# VM3300_V0_1.net
KiCad netlist of a schematic drawn in Altium Designer
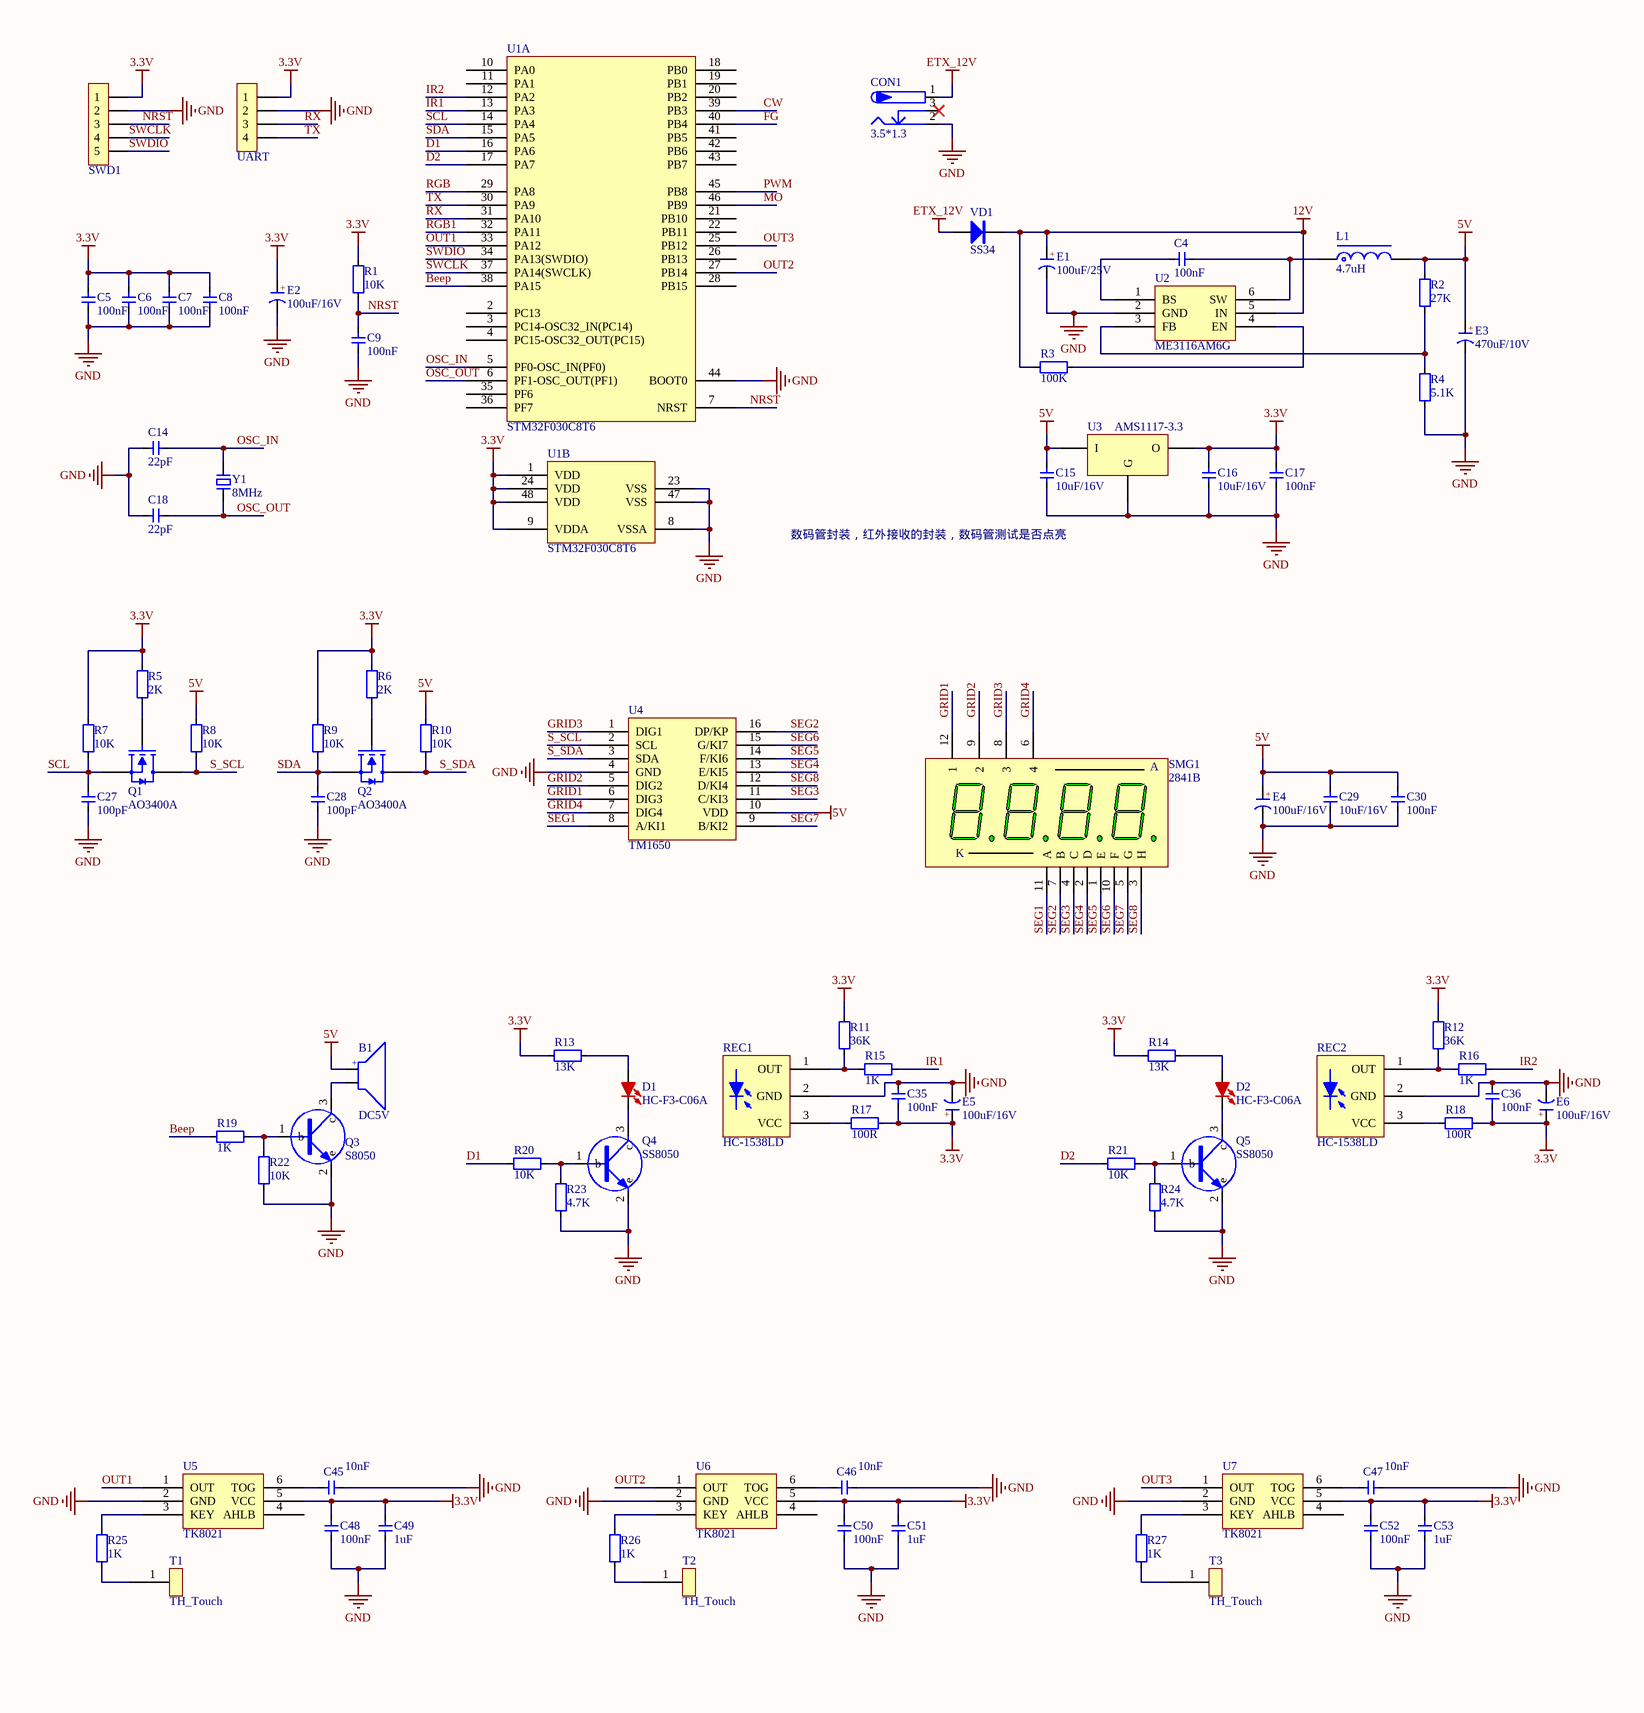
[diagram p0: VM3300_V0.1.SchDoc, left]
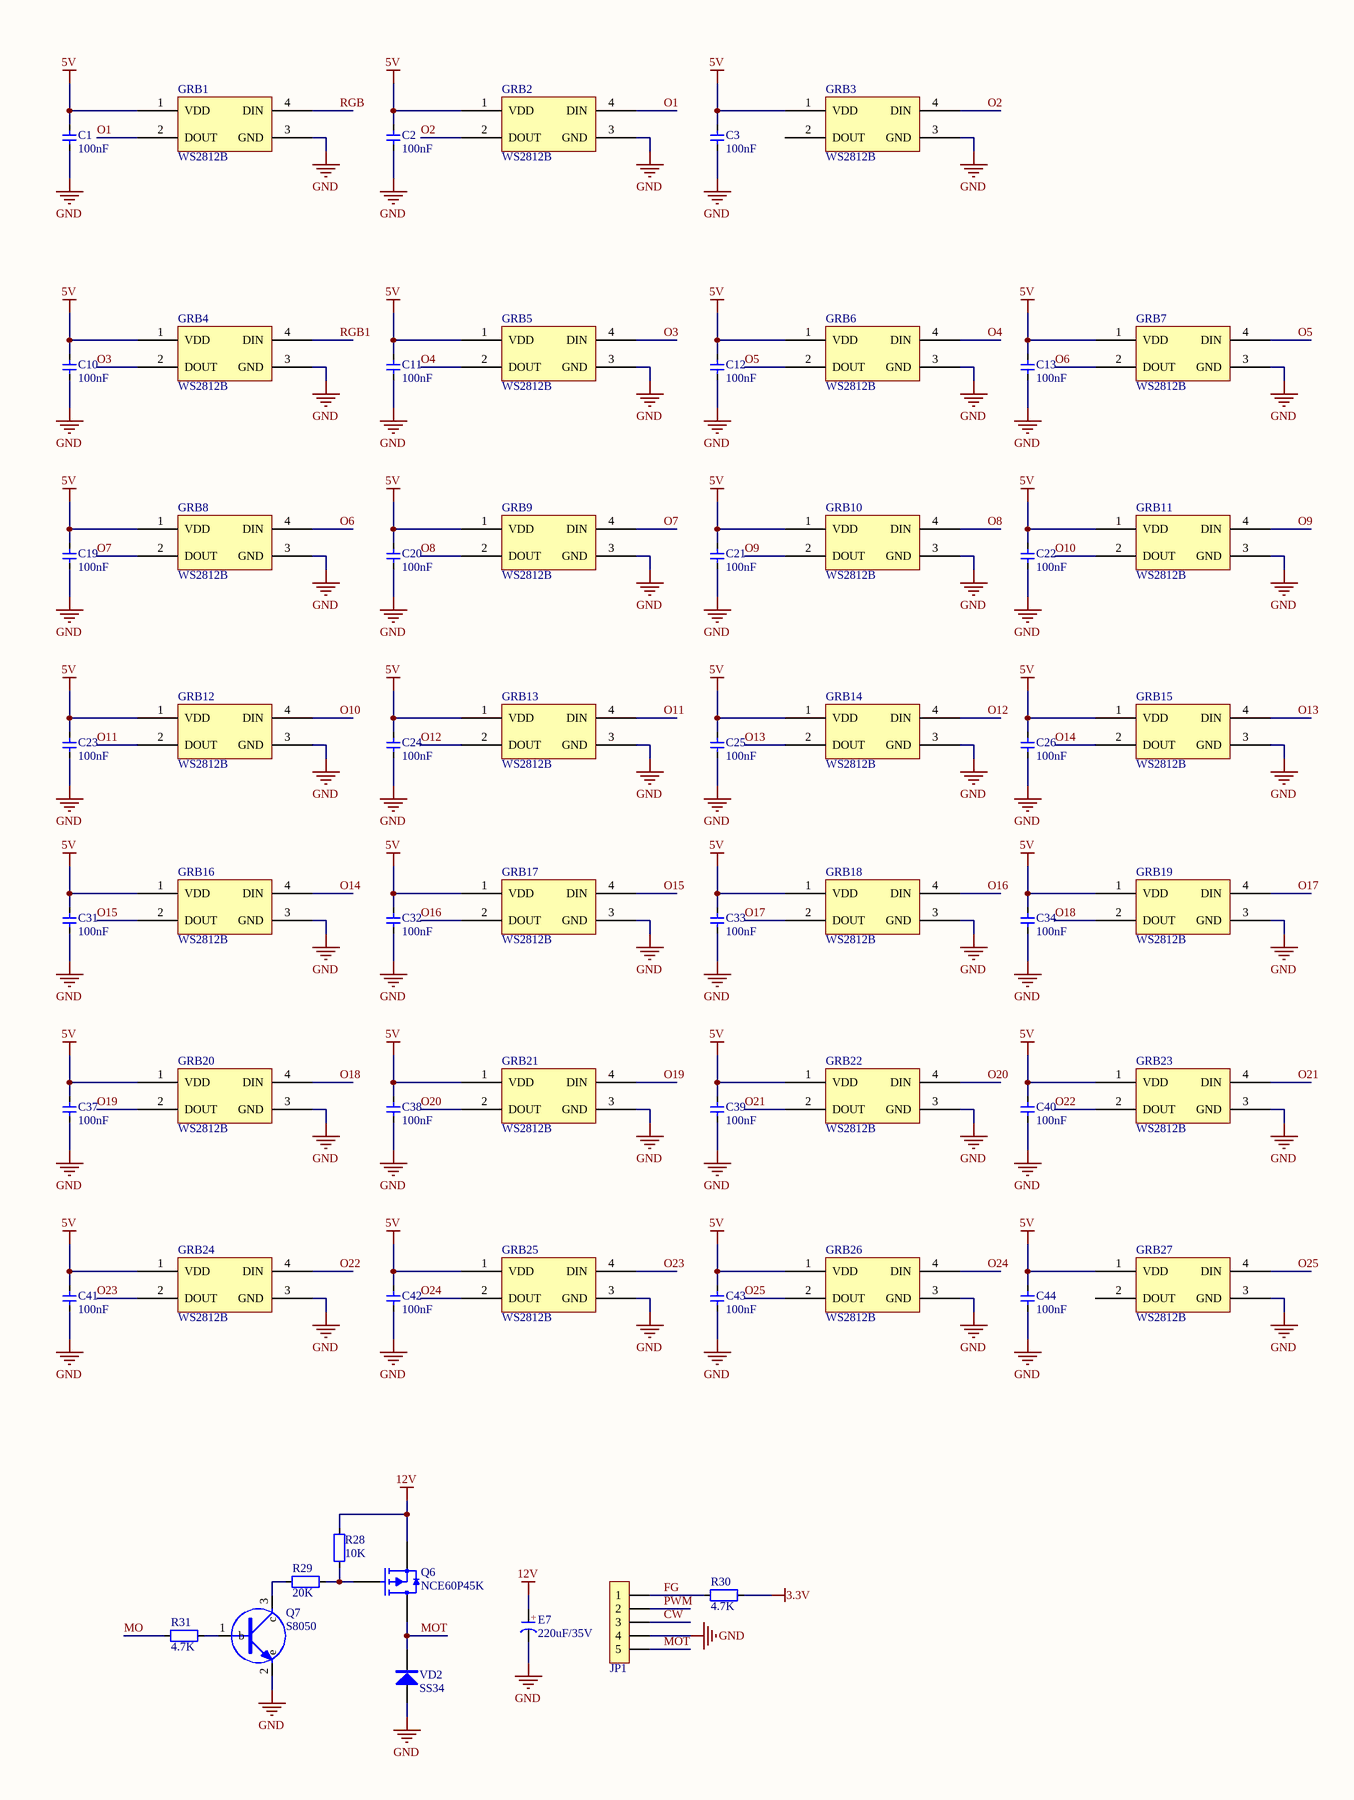
[diagram p1: VM3300_V0.1.SchDoc, right]

(export (version "E")
  (design (tool "Eeschema 10.0.6"))
  (components
    (comp (ref "B1")
      (value "DC5V")
      (footprint "BEEP 7.6x12x7.5")
      (description "蜂鸣器")
      (fields (field (name "版权归属") "源创客"))
      (libsource (lib "模块器件") (part "BEEP"))
    )
    (comp (ref "C1")
      (value "100nF")
      (footprint "C 0603")
      (description "无极性贴片电容")
      (fields (field (name "版权归属") "源创客"))
      (libsource (lib "电容") (part "C"))
    )
    (comp (ref "C2")
      (value "100nF")
      (footprint "C 0603")
      (description "无极性贴片电容")
      (fields (field (name "版权归属") "源创客"))
      (libsource (lib "电容") (part "C"))
    )
    (comp (ref "C3")
      (value "100nF")
      (footprint "C 0603")
      (description "无极性贴片电容")
      (fields (field (name "版权归属") "源创客"))
      (libsource (lib "电容") (part "C"))
    )
    (comp (ref "C4")
      (value "100nF")
      (footprint "C 0603")
      (description "无极性贴片电容")
      (fields (field (name "版权归属") "源创客"))
      (libsource (lib "电容") (part "C"))
    )
    (comp (ref "C5")
      (value "100nF")
      (footprint "C 0603")
      (description "无极性贴片电容")
      (fields (field (name "版权归属") "源创客"))
      (libsource (lib "电容") (part "C"))
    )
    (comp (ref "C6")
      (value "100nF")
      (footprint "C 0603")
      (description "无极性贴片电容")
      (fields (field (name "版权归属") "源创客"))
      (libsource (lib "电容") (part "C"))
    )
    (comp (ref "C7")
      (value "100nF")
      (footprint "C 0603")
      (description "无极性贴片电容")
      (fields (field (name "版权归属") "源创客"))
      (libsource (lib "电容") (part "C"))
    )
    (comp (ref "C8")
      (value "100nF")
      (footprint "C 0603")
      (description "无极性贴片电容")
      (fields (field (name "版权归属") "源创客"))
      (libsource (lib "电容") (part "C"))
    )
    (comp (ref "C9")
      (value "100nF")
      (footprint "C 0603")
      (description "无极性贴片电容")
      (fields (field (name "版权归属") "源创客"))
      (libsource (lib "电容") (part "C"))
    )
    (comp (ref "C10")
      (value "100nF")
      (footprint "C 0603")
      (description "无极性贴片电容")
      (fields (field (name "版权归属") "源创客"))
      (libsource (lib "电容") (part "C"))
    )
    (comp (ref "C11")
      (value "100nF")
      (footprint "C 0603")
      (description "无极性贴片电容")
      (fields (field (name "版权归属") "源创客"))
      (libsource (lib "电容") (part "C"))
    )
    (comp (ref "C12")
      (value "100nF")
      (footprint "C 0603")
      (description "无极性贴片电容")
      (fields (field (name "版权归属") "源创客"))
      (libsource (lib "电容") (part "C"))
    )
    (comp (ref "C13")
      (value "100nF")
      (footprint "C 0603")
      (description "无极性贴片电容")
      (fields (field (name "版权归属") "源创客"))
      (libsource (lib "电容") (part "C"))
    )
    (comp (ref "C14")
      (value "22pF")
      (footprint "C 0603")
      (description "无极性贴片电容")
      (fields (field (name "版权归属") "源创客"))
      (libsource (lib "电容") (part "C"))
    )
    (comp (ref "C15")
      (value "10uF/16V")
      (footprint "C 0805")
      (description "无极性贴片电容")
      (fields (field (name "版权归属") "源创客"))
      (libsource (lib "电容") (part "C"))
    )
    (comp (ref "C16")
      (value "10uF/16V")
      (footprint "C 0805")
      (description "无极性贴片电容")
      (fields (field (name "版权归属") "源创客"))
      (libsource (lib "电容") (part "C"))
    )
    (comp (ref "C17")
      (value "100nF")
      (footprint "C 0603")
      (description "无极性贴片电容")
      (fields (field (name "版权归属") "源创客"))
      (libsource (lib "电容") (part "C"))
    )
    (comp (ref "C18")
      (value "22pF")
      (footprint "C 0603")
      (description "无极性贴片电容")
      (fields (field (name "版权归属") "源创客"))
      (libsource (lib "电容") (part "C"))
    )
    (comp (ref "C19")
      (value "100nF")
      (footprint "C 0603")
      (description "无极性贴片电容")
      (fields (field (name "版权归属") "源创客"))
      (libsource (lib "电容") (part "C"))
    )
    (comp (ref "C20")
      (value "100nF")
      (footprint "C 0603")
      (description "无极性贴片电容")
      (fields (field (name "版权归属") "源创客"))
      (libsource (lib "电容") (part "C"))
    )
    (comp (ref "C21")
      (value "100nF")
      (footprint "C 0603")
      (description "无极性贴片电容")
      (fields (field (name "版权归属") "源创客"))
      (libsource (lib "电容") (part "C"))
    )
    (comp (ref "C22")
      (value "100nF")
      (footprint "C 0603")
      (description "无极性贴片电容")
      (fields (field (name "版权归属") "源创客"))
      (libsource (lib "电容") (part "C"))
    )
    (comp (ref "C23")
      (value "100nF")
      (footprint "C 0603")
      (description "无极性贴片电容")
      (fields (field (name "版权归属") "源创客"))
      (libsource (lib "电容") (part "C"))
    )
    (comp (ref "C24")
      (value "100nF")
      (footprint "C 0603")
      (description "无极性贴片电容")
      (fields (field (name "版权归属") "源创客"))
      (libsource (lib "电容") (part "C"))
    )
    (comp (ref "C25")
      (value "100nF")
      (footprint "C 0603")
      (description "无极性贴片电容")
      (fields (field (name "版权归属") "源创客"))
      (libsource (lib "电容") (part "C"))
    )
    (comp (ref "C26")
      (value "100nF")
      (footprint "C 0603")
      (description "无极性贴片电容")
      (fields (field (name "版权归属") "源创客"))
      (libsource (lib "电容") (part "C"))
    )
    (comp (ref "C27")
      (value "100pF")
      (footprint "C 0603")
      (description "无极性贴片电容")
      (fields (field (name "版权归属") "源创客"))
      (libsource (lib "电容") (part "C"))
    )
    (comp (ref "C28")
      (value "100pF")
      (footprint "C 0603")
      (description "无极性贴片电容")
      (fields (field (name "版权归属") "源创客"))
      (libsource (lib "电容") (part "C"))
    )
    (comp (ref "C29")
      (value "10uF/16V")
      (footprint "C 0805")
      (description "无极性贴片电容")
      (fields (field (name "版权归属") "源创客"))
      (libsource (lib "电容") (part "C"))
    )
    (comp (ref "C30")
      (value "100nF")
      (footprint "C 0603")
      (description "无极性贴片电容")
      (fields (field (name "版权归属") "源创客"))
      (libsource (lib "电容") (part "C"))
    )
    (comp (ref "C31")
      (value "100nF")
      (footprint "C 0603")
      (description "无极性贴片电容")
      (fields (field (name "版权归属") "源创客"))
      (libsource (lib "电容") (part "C"))
    )
    (comp (ref "C32")
      (value "100nF")
      (footprint "C 0603")
      (description "无极性贴片电容")
      (fields (field (name "版权归属") "源创客"))
      (libsource (lib "电容") (part "C"))
    )
    (comp (ref "C33")
      (value "100nF")
      (footprint "C 0603")
      (description "无极性贴片电容")
      (fields (field (name "版权归属") "源创客"))
      (libsource (lib "电容") (part "C"))
    )
    (comp (ref "C34")
      (value "100nF")
      (footprint "C 0603")
      (description "无极性贴片电容")
      (fields (field (name "版权归属") "源创客"))
      (libsource (lib "电容") (part "C"))
    )
    (comp (ref "C35")
      (value "100nF")
      (footprint "C 0603")
      (description "无极性贴片电容")
      (fields (field (name "版权归属") "源创客"))
      (libsource (lib "电容") (part "C"))
    )
    (comp (ref "C36")
      (value "100nF")
      (footprint "C 0603")
      (description "无极性贴片电容")
      (fields (field (name "版权归属") "源创客"))
      (libsource (lib "电容") (part "C"))
    )
    (comp (ref "C37")
      (value "100nF")
      (footprint "C 0603")
      (description "无极性贴片电容")
      (fields (field (name "版权归属") "源创客"))
      (libsource (lib "电容") (part "C"))
    )
    (comp (ref "C38")
      (value "100nF")
      (footprint "C 0603")
      (description "无极性贴片电容")
      (fields (field (name "版权归属") "源创客"))
      (libsource (lib "电容") (part "C"))
    )
    (comp (ref "C39")
      (value "100nF")
      (footprint "C 0603")
      (description "无极性贴片电容")
      (fields (field (name "版权归属") "源创客"))
      (libsource (lib "电容") (part "C"))
    )
    (comp (ref "C40")
      (value "100nF")
      (footprint "C 0603")
      (description "无极性贴片电容")
      (fields (field (name "版权归属") "源创客"))
      (libsource (lib "电容") (part "C"))
    )
    (comp (ref "C41")
      (value "100nF")
      (footprint "C 0603")
      (description "无极性贴片电容")
      (fields (field (name "版权归属") "源创客"))
      (libsource (lib "电容") (part "C"))
    )
    (comp (ref "C42")
      (value "100nF")
      (footprint "C 0603")
      (description "无极性贴片电容")
      (fields (field (name "版权归属") "源创客"))
      (libsource (lib "电容") (part "C"))
    )
    (comp (ref "C43")
      (value "100nF")
      (footprint "C 0603")
      (description "无极性贴片电容")
      (fields (field (name "版权归属") "源创客"))
      (libsource (lib "电容") (part "C"))
    )
    (comp (ref "C44")
      (value "100nF")
      (footprint "C 0603")
      (description "无极性贴片电容")
      (fields (field (name "版权归属") "源创客"))
      (libsource (lib "电容") (part "C"))
    )
    (comp (ref "C45")
      (value "10nF")
      (footprint "C 0603")
      (description "无极性贴片电容")
      (fields (field (name "版权归属") "源创客"))
      (libsource (lib "电容") (part "C"))
    )
    (comp (ref "C46")
      (value "10nF")
      (footprint "C 0603")
      (description "无极性贴片电容")
      (fields (field (name "版权归属") "源创客"))
      (libsource (lib "电容") (part "C"))
    )
    (comp (ref "C47")
      (value "10nF")
      (footprint "C 0603")
      (description "无极性贴片电容")
      (fields (field (name "版权归属") "源创客"))
      (libsource (lib "电容") (part "C"))
    )
    (comp (ref "C48")
      (value "100nF")
      (footprint "C 0603")
      (description "无极性贴片电容")
      (fields (field (name "版权归属") "源创客"))
      (libsource (lib "电容") (part "C"))
    )
    (comp (ref "C49")
      (value "1uF")
      (footprint "C 0603")
      (description "无极性贴片电容")
      (fields (field (name "版权归属") "源创客"))
      (libsource (lib "电容") (part "C"))
    )
    (comp (ref "C50")
      (value "100nF")
      (footprint "C 0603")
      (description "无极性贴片电容")
      (fields (field (name "版权归属") "源创客"))
      (libsource (lib "电容") (part "C"))
    )
    (comp (ref "C51")
      (value "1uF")
      (footprint "C 0603")
      (description "无极性贴片电容")
      (fields (field (name "版权归属") "源创客"))
      (libsource (lib "电容") (part "C"))
    )
    (comp (ref "C52")
      (value "100nF")
      (footprint "C 0603")
      (description "无极性贴片电容")
      (fields (field (name "版权归属") "源创客"))
      (libsource (lib "电容") (part "C"))
    )
    (comp (ref "C53")
      (value "1uF")
      (footprint "C 0603")
      (description "无极性贴片电容")
      (fields (field (name "版权归属") "源创客"))
      (libsource (lib "电容") (part "C"))
    )
    (comp (ref "CON1")
      (value "3.5*1.3")
      (footprint "DC-005")
      (description "低压电源接口")
      (fields (field (name "版权归属") "源创客"))
      (libsource (lib "接口类") (part "P-DC"))
    )
    (comp (ref "D1")
      (value "HC-F3-C06A")
      (footprint "HC-F3-C06A")
      (description "红外发射管")
      (libsource (lib "传感器") (part "HC-F3-C06A"))
    )
    (comp (ref "D2")
      (value "HC-F3-C06A")
      (footprint "HC-F3-C06A")
      (description "红外发射管")
      (libsource (lib "传感器") (part "HC-F3-C06A"))
    )
    (comp (ref "E1")
      (value "100uF/25V")
      (footprint "CAP 2.0*5*11 - BK")
      (description "直插电解电容")
      (fields (field (name "版权归属") "源创客"))
      (libsource (lib "电容") (part "C-CAP"))
    )
    (comp (ref "E2")
      (value "100uF/16V")
      (footprint "CAP 2.0*5*11 - BK")
      (description "直插电解电容")
      (fields (field (name "版权归属") "源创客"))
      (libsource (lib "电容") (part "C-CAP"))
    )
    (comp (ref "E3")
      (value "470uF/10V")
      (footprint "CAP 2.5*6.3*11.2 - BK")
      (description "直插电解电容")
      (fields (field (name "版权归属") "源创客"))
      (libsource (lib "电容") (part "C-CAP"))
    )
    (comp (ref "E4")
      (value "100uF/16V")
      (footprint "CAP 2.0*5*11 - BK")
      (description "直插电解电容")
      (fields (field (name "版权归属") "源创客"))
      (libsource (lib "电容") (part "C-CAP"))
    )
    (comp (ref "E5")
      (value "100uF/16V")
      (footprint "CAP 2.0*5*11 - BK")
      (description "直插电解电容")
      (fields (field (name "版权归属") "源创客"))
      (libsource (lib "电容") (part "C-CAP"))
    )
    (comp (ref "E6")
      (value "100uF/16V")
      (footprint "CAP 2.0*5*11 - BK")
      (description "直插电解电容")
      (fields (field (name "版权归属") "源创客"))
      (libsource (lib "电容") (part "C-CAP"))
    )
    (comp (ref "E7")
      (value "220uF/35V")
      (footprint "CAP 3.5*8*11.5 - BK")
      (description "直插电解电容")
      (fields (field (name "版权归属") "源创客"))
      (libsource (lib "电容") (part "C-CAP"))
    )
    (comp (ref "GRB1") (value "WS2812B") (footprint "WS2812B-3528") (libsource (lib "LED") (part "WS2812B")))
    (comp (ref "GRB2") (value "WS2812B") (footprint "WS2812B-3528") (libsource (lib "LED") (part "WS2812B")))
    (comp (ref "GRB3") (value "WS2812B") (footprint "WS2812B-3528") (libsource (lib "LED") (part "WS2812B")))
    (comp (ref "GRB4") (value "WS2812B") (footprint "WS2812B-3528") (libsource (lib "LED") (part "WS2812B")))
    (comp (ref "GRB5") (value "WS2812B") (footprint "WS2812B-3528") (libsource (lib "LED") (part "WS2812B")))
    (comp (ref "GRB6") (value "WS2812B") (footprint "WS2812B-3528") (libsource (lib "LED") (part "WS2812B")))
    (comp (ref "GRB7") (value "WS2812B") (footprint "WS2812B-3528") (libsource (lib "LED") (part "WS2812B")))
    (comp (ref "GRB8") (value "WS2812B") (footprint "WS2812B-3528") (libsource (lib "LED") (part "WS2812B")))
    (comp (ref "GRB9") (value "WS2812B") (footprint "WS2812B-3528") (libsource (lib "LED") (part "WS2812B")))
    (comp (ref "GRB10") (value "WS2812B") (footprint "WS2812B-3528") (libsource (lib "LED") (part "WS2812B")))
    (comp (ref "GRB11") (value "WS2812B") (footprint "WS2812B-3528") (libsource (lib "LED") (part "WS2812B")))
    (comp (ref "GRB12") (value "WS2812B") (footprint "WS2812B-3528") (libsource (lib "LED") (part "WS2812B")))
    (comp (ref "GRB13") (value "WS2812B") (footprint "WS2812B-3528") (libsource (lib "LED") (part "WS2812B")))
    (comp (ref "GRB14") (value "WS2812B") (footprint "WS2812B-3528") (libsource (lib "LED") (part "WS2812B")))
    (comp (ref "GRB15") (value "WS2812B") (footprint "WS2812B-3528") (libsource (lib "LED") (part "WS2812B")))
    (comp (ref "GRB16") (value "WS2812B") (footprint "WS2812B-3528") (libsource (lib "LED") (part "WS2812B")))
    (comp (ref "GRB17") (value "WS2812B") (footprint "WS2812B-3528") (libsource (lib "LED") (part "WS2812B")))
    (comp (ref "GRB18") (value "WS2812B") (footprint "WS2812B-3528") (libsource (lib "LED") (part "WS2812B")))
    (comp (ref "GRB19") (value "WS2812B") (footprint "WS2812B-3528") (libsource (lib "LED") (part "WS2812B")))
    (comp (ref "GRB20") (value "WS2812B") (footprint "WS2812B-3528") (libsource (lib "LED") (part "WS2812B")))
    (comp (ref "GRB21") (value "WS2812B") (footprint "WS2812B-3528") (libsource (lib "LED") (part "WS2812B")))
    (comp (ref "GRB22") (value "WS2812B") (footprint "WS2812B-3528") (libsource (lib "LED") (part "WS2812B")))
    (comp (ref "GRB23") (value "WS2812B") (footprint "WS2812B-3528") (libsource (lib "LED") (part "WS2812B")))
    (comp (ref "GRB24") (value "WS2812B") (footprint "WS2812B-3528") (libsource (lib "LED") (part "WS2812B")))
    (comp (ref "GRB25") (value "WS2812B") (footprint "WS2812B-3528") (libsource (lib "LED") (part "WS2812B")))
    (comp (ref "GRB26") (value "WS2812B") (footprint "WS2812B-3528") (libsource (lib "LED") (part "WS2812B")))
    (comp (ref "GRB27") (value "WS2812B") (footprint "WS2812B-3528") (libsource (lib "LED") (part "WS2812B")))
    (comp (ref "JP1")
      (value "HDR-1X5")
      (footprint "XH2.54-5P")
      (description "5P接插件")
      (fields (field (name "版权归属") "源创客"))
      (libsource (lib "排针-排母") (part "Header 5"))
    )
    (comp (ref "L1")
      (value "4.7uH")
      (footprint "CD32")
      (description "贴片功率电感")
      (fields (field (name "版权归属") "源创客"))
      (libsource (lib "电感") (part "L-CD"))
    )
    (comp (ref "Q1")
      (value "AO3400A")
      (footprint "SOT23-3")
      (description "N-MOS")
      (libsource (lib "三极管") (part "AO3400A"))
    )
    (comp (ref "Q2")
      (value "AO3400A")
      (footprint "SOT23-3")
      (description "N-MOS")
      (libsource (lib "三极管") (part "AO3400A"))
    )
    (comp (ref "Q3") (value "S8050") (footprint "SOT23-3L") (libsource (lib "三极管") (part "NPN")))
    (comp (ref "Q4") (value "SS8050") (footprint "SOT23-3L") (libsource (lib "三极管") (part "NPN")))
    (comp (ref "Q5") (value "SS8050") (footprint "SOT23-3L") (libsource (lib "三极管") (part "NPN")))
    (comp (ref "Q6")
      (value "NCE60P45K")
      (footprint "NCE_MOS")
      (description "NCE系类的MOS")
      (libsource (lib "三极管") (part "NCE_MOS"))
    )
    (comp (ref "Q7") (value "S8050") (footprint "SOT23-3L") (libsource (lib "三极管") (part "NPN")))
    (comp (ref "R1")
      (value "10K")
      (footprint "R 0603")
      (description "贴片电阻")
      (fields (field (name "版权归属") "源创客"))
      (libsource (lib "电阻") (part "R"))
    )
    (comp (ref "R2")
      (value "27K")
      (footprint "R 0603")
      (description "贴片电阻")
      (fields (field (name "版权归属") "源创客"))
      (libsource (lib "电阻") (part "R"))
    )
    (comp (ref "R3")
      (value "100K")
      (footprint "R 0603")
      (description "贴片电阻")
      (fields (field (name "版权归属") "源创客"))
      (libsource (lib "") (part "R_1"))
    )
    (comp (ref "R4")
      (value "5.1K")
      (footprint "R 0603")
      (description "贴片电阻")
      (fields (field (name "版权归属") "源创客"))
      (libsource (lib "电阻") (part "R"))
    )
    (comp (ref "R5")
      (value "2K")
      (footprint "R 0603")
      (description "贴片电阻")
      (fields (field (name "版权归属") "源创客"))
      (libsource (lib "电阻") (part "R"))
    )
    (comp (ref "R6")
      (value "2K")
      (footprint "R 0603")
      (description "贴片电阻")
      (fields (field (name "版权归属") "源创客"))
      (libsource (lib "电阻") (part "R"))
    )
    (comp (ref "R7")
      (value "10K")
      (footprint "R 0603")
      (description "贴片电阻")
      (fields (field (name "版权归属") "源创客"))
      (libsource (lib "电阻") (part "R"))
    )
    (comp (ref "R8")
      (value "10K")
      (footprint "R 0603")
      (description "贴片电阻")
      (fields (field (name "版权归属") "源创客"))
      (libsource (lib "电阻") (part "R"))
    )
    (comp (ref "R9")
      (value "10K")
      (footprint "R 0603")
      (description "贴片电阻")
      (fields (field (name "版权归属") "源创客"))
      (libsource (lib "电阻") (part "R"))
    )
    (comp (ref "R10")
      (value "10K")
      (footprint "R 0603")
      (description "贴片电阻")
      (fields (field (name "版权归属") "源创客"))
      (libsource (lib "电阻") (part "R"))
    )
    (comp (ref "R11")
      (value "36K")
      (footprint "R 0603")
      (description "贴片电阻")
      (fields (field (name "版权归属") "源创客"))
      (libsource (lib "电阻") (part "R"))
    )
    (comp (ref "R12")
      (value "36K")
      (footprint "R 0603")
      (description "贴片电阻")
      (fields (field (name "版权归属") "源创客"))
      (libsource (lib "电阻") (part "R"))
    )
    (comp (ref "R13")
      (value "13K")
      (footprint "R 0603")
      (description "贴片电阻")
      (fields (field (name "版权归属") "源创客"))
      (libsource (lib "") (part "R_1"))
    )
    (comp (ref "R14")
      (value "13K")
      (footprint "R 0603")
      (description "贴片电阻")
      (fields (field (name "版权归属") "源创客"))
      (libsource (lib "") (part "R_1"))
    )
    (comp (ref "R15")
      (value "1K")
      (footprint "R 0603")
      (description "贴片电阻")
      (fields (field (name "版权归属") "源创客"))
      (libsource (lib "") (part "R_1"))
    )
    (comp (ref "R16")
      (value "1K")
      (footprint "R 0603")
      (description "贴片电阻")
      (fields (field (name "版权归属") "源创客"))
      (libsource (lib "") (part "R_1"))
    )
    (comp (ref "R17")
      (value "100R")
      (footprint "R 0603")
      (description "贴片电阻")
      (fields (field (name "版权归属") "源创客"))
      (libsource (lib "") (part "R_1"))
    )
    (comp (ref "R18")
      (value "100R")
      (footprint "R 0603")
      (description "贴片电阻")
      (fields (field (name "版权归属") "源创客"))
      (libsource (lib "") (part "R_1"))
    )
    (comp (ref "R19")
      (value "1K")
      (footprint "R 0603")
      (description "贴片电阻")
      (fields (field (name "版权归属") "源创客"))
      (libsource (lib "") (part "R_1"))
    )
    (comp (ref "R20")
      (value "10K")
      (footprint "R 0603")
      (description "贴片电阻")
      (fields (field (name "版权归属") "源创客"))
      (libsource (lib "") (part "R_1"))
    )
    (comp (ref "R21")
      (value "10K")
      (footprint "R 0603")
      (description "贴片电阻")
      (fields (field (name "版权归属") "源创客"))
      (libsource (lib "") (part "R_1"))
    )
    (comp (ref "R22")
      (value "10K")
      (footprint "R 0603")
      (description "贴片电阻")
      (fields (field (name "版权归属") "源创客"))
      (libsource (lib "电阻") (part "R"))
    )
    (comp (ref "R23")
      (value "4.7K")
      (footprint "R 0603")
      (description "贴片电阻")
      (fields (field (name "版权归属") "源创客"))
      (libsource (lib "电阻") (part "R"))
    )
    (comp (ref "R24")
      (value "4.7K")
      (footprint "R 0603")
      (description "贴片电阻")
      (fields (field (name "版权归属") "源创客"))
      (libsource (lib "电阻") (part "R"))
    )
    (comp (ref "R25")
      (value "1K")
      (footprint "R 0603")
      (description "贴片电阻")
      (fields (field (name "版权归属") "源创客"))
      (libsource (lib "电阻") (part "R"))
    )
    (comp (ref "R26")
      (value "1K")
      (footprint "R 0603")
      (description "贴片电阻")
      (fields (field (name "版权归属") "源创客"))
      (libsource (lib "电阻") (part "R"))
    )
    (comp (ref "R27")
      (value "1K")
      (footprint "R 0603")
      (description "贴片电阻")
      (fields (field (name "版权归属") "源创客"))
      (libsource (lib "电阻") (part "R"))
    )
    (comp (ref "R28")
      (value "10K")
      (footprint "R 0603")
      (description "贴片电阻")
      (fields (field (name "版权归属") "源创客"))
      (libsource (lib "电阻") (part "R"))
    )
    (comp (ref "R29")
      (value "20K")
      (footprint "R 0603")
      (description "贴片电阻")
      (fields (field (name "版权归属") "源创客"))
      (libsource (lib "") (part "R_1"))
    )
    (comp (ref "R30")
      (value "4.7K")
      (footprint "R 0603")
      (description "贴片电阻")
      (fields (field (name "版权归属") "源创客"))
      (libsource (lib "") (part "R_1"))
    )
    (comp (ref "R31")
      (value "4.7K")
      (footprint "R 0603")
      (description "贴片电阻")
      (fields (field (name "版权归属") "源创客"))
      (libsource (lib "") (part "R_1"))
    )
    (comp (ref "REC1")
      (value "HC-1538LD")
      (footprint "HC-1538LD")
      (description "红外接收管")
      (libsource (lib "传感器") (part "HC-1538LD"))
    )
    (comp (ref "REC2")
      (value "HC-1538LD")
      (footprint "HC-1538LD")
      (description "红外接收管")
      (libsource (lib "传感器") (part "HC-1538LD"))
    )
    (comp (ref "SMG1")
      (value "2841B")
      (footprint "SMG 0.28-4P_B")
      (description "0.28寸4位共阳数码管")
      (fields (field (name "版权归属") "源创客"))
      (libsource (lib "显示器件") (part "2841B"))
    )
    (comp (ref "SWD1")
      (value "HDR-1X5")
      (footprint "SWD_JOANLAB")
      (description "5P接插件")
      (fields (field (name "版权归属") "源创客"))
      (libsource (lib "排针-排母") (part "Header 5"))
    )
    (comp (ref "T1")
      (value "TH_Touch")
      (footprint "TH_Touch")
      (description "触摸弹簧，用于触摸感应")
      (libsource (lib "模块器件") (part "TH_Touch"))
    )
    (comp (ref "T2")
      (value "TH_Touch")
      (footprint "TH_Touch")
      (description "触摸弹簧，用于触摸感应")
      (libsource (lib "模块器件") (part "TH_Touch"))
    )
    (comp (ref "T3")
      (value "TH_Touch")
      (footprint "TH_Touch")
      (description "触摸弹簧，用于触摸感应")
      (libsource (lib "模块器件") (part "TH_Touch"))
    )
    (comp (ref "U1")
      (value "STM32F030C8T6")
      (footprint "STM32F030C8T6")
      (libsource (lib "STM32系列单片机") (part "STM32F030C8T6"))
    )
    (comp (ref "U2")
      (value "ME3116AM6G")
      (footprint "ME3116AM6G")
      (description "DC-DC电源芯片  24-40V->5V")
      (libsource (lib "变压器") (part "ME3116AM6G"))
    )
    (comp (ref "U3")
      (value "AMS1117-3.3")
      (footprint "AMS1117-3.3")
      (description "转3.3V电压")
      (libsource (lib "变压器") (part "AMS1117-3.3"))
    )
    (comp (ref "U4")
      (value "TM1650")
      (footprint "TM1650")
      (description "TM1650是一种带键盘扫描接口的LED（发光二极管显示器）驱动控制专用IC,内部集成有MCU\r\n数字接口、数据锁存器、LED驱动、键盘扫描等电路。")
      (libsource (lib "显示芯片") (part "TM1650"))
    )
    (comp (ref "U5")
      (value "TK8021")
      (footprint "TK8021")
      (description "单通道自校正触摸感应芯片")
      (libsource (lib "常用芯片") (part "TTP2233"))
    )
    (comp (ref "U6")
      (value "TK8021")
      (footprint "TK8021")
      (description "单通道自校正触摸感应芯片")
      (libsource (lib "常用芯片") (part "TTP2233"))
    )
    (comp (ref "U7")
      (value "TK8021")
      (footprint "TK8021")
      (description "单通道自校正触摸感应芯片")
      (libsource (lib "常用芯片") (part "TTP2233"))
    )
    (comp (ref "UART")
      (value "HDR-1X4")
      (footprint "XH2.54-4P")
      (description "4P接插件")
      (fields (field (name "版权归属") "源创客"))
      (libsource (lib "排针-排母") (part "Header 4"))
    )
    (comp (ref "VD1")
      (value "SS34")
      (footprint "SMA")
      (description "肖特基二极管")
      (fields (field (name "版权归属") "源创客"))
      (libsource (lib "二极管-整流桥") (part "SS34"))
    )
    (comp (ref "VD2")
      (value "SS34")
      (footprint "SMA")
      (description "肖特基二极管")
      (fields (field (name "版权归属") "源创客"))
      (libsource (lib "二极管-整流桥") (part "SS34"))
    )
    (comp (ref "Y1")
      (value "8MHz")
      (footprint "XTAL-49S SMD")
      (description "2脚晶振")
      (fields (field (name "版权归属") "源创客"))
      (libsource (lib "晶振") (part "XTAL-2"))
    )
  )
  (nets
    (net (code "1") (name "/Beep") (class "Default")
      (node (ref "R19") (pin "1") (pinfunction "1_1") (pintype "passive"))
      (node (ref "U1") (pin "38") (pinfunction "PA15_38") (pintype "passive"))
    )
    (net (code "2") (name "/CW") (class "Default")
      (node (ref "JP1") (pin "3") (pinfunction "3_3") (pintype "passive"))
      (node (ref "U1") (pin "39") (pinfunction "PB3_39") (pintype "passive"))
    )
    (net (code "3") (name "/D1") (class "Default")
      (node (ref "R20") (pin "1") (pinfunction "1_1") (pintype "passive"))
      (node (ref "U1") (pin "16") (pinfunction "PA6_16") (pintype "passive"))
    )
    (net (code "4") (name "/D2") (class "Default")
      (node (ref "R21") (pin "1") (pinfunction "1_1") (pintype "passive"))
      (node (ref "U1") (pin "17") (pinfunction "PA7_17") (pintype "passive"))
    )
    (net (code "5") (name "/FG") (class "Default")
      (node (ref "JP1") (pin "1") (pinfunction "1_1") (pintype "passive"))
      (node (ref "R30") (pin "1") (pinfunction "1_1") (pintype "passive"))
      (node (ref "U1") (pin "40") (pinfunction "PB4_40") (pintype "passive"))
    )
    (net (code "6") (name "/GRID1") (class "Default")
      (node (ref "SMG1") (pin "12") (pinfunction "1_12") (pintype "passive"))
      (node (ref "U4") (pin "6") (pinfunction "DIG3_6") (pintype "passive"))
    )
    (net (code "7") (name "/GRID2") (class "Default")
      (node (ref "SMG1") (pin "9") (pinfunction "2_9") (pintype "passive"))
      (node (ref "U4") (pin "5") (pinfunction "DIG2_5") (pintype "passive"))
    )
    (net (code "8") (name "/GRID3") (class "Default")
      (node (ref "SMG1") (pin "8") (pinfunction "3_8") (pintype "passive"))
      (node (ref "U4") (pin "1") (pinfunction "DIG1_1") (pintype "passive"))
    )
    (net (code "9") (name "/GRID4") (class "Default")
      (node (ref "SMG1") (pin "6") (pinfunction "4_6") (pintype "passive"))
      (node (ref "U4") (pin "7") (pinfunction "DIG4_7") (pintype "passive"))
    )
    (net (code "10") (name "/IR1") (class "Default")
      (node (ref "R15") (pin "2") (pinfunction "2_2") (pintype "passive"))
      (node (ref "U1") (pin "13") (pinfunction "PA3_13") (pintype "passive"))
    )
    (net (code "11") (name "/IR2") (class "Default")
      (node (ref "R16") (pin "2") (pinfunction "2_2") (pintype "passive"))
      (node (ref "U1") (pin "12") (pinfunction "PA2_12") (pintype "passive"))
    )
    (net (code "12") (name "/MO") (class "Default")
      (node (ref "R31") (pin "1") (pinfunction "1_1") (pintype "passive"))
      (node (ref "U1") (pin "46") (pinfunction "PB9_46") (pintype "passive"))
    )
    (net (code "13") (name "/MOT") (class "Default")
      (node (ref "JP1") (pin "5") (pinfunction "5_5") (pintype "passive"))
      (node (ref "Q6") (pin "2") (pinfunction "D_2") (pintype "passive"))
      (node (ref "VD2") (pin "2") (pinfunction "K_2") (pintype "passive"))
    )
    (net (code "14") (name "/NRST") (class "Default")
      (node (ref "C9") (pin "2") (pinfunction "2_2") (pintype "passive"))
      (node (ref "R1") (pin "1") (pinfunction "1_1") (pintype "passive"))
      (node (ref "SWD1") (pin "3") (pinfunction "3_3") (pintype "passive"))
      (node (ref "U1") (pin "7") (pinfunction "NRST_7") (pintype "passive"))
    )
    (net (code "15") (name "/O1") (class "Default")
      (node (ref "GRB1") (pin "2") (pinfunction "DOUT_2") (pintype "passive"))
      (node (ref "GRB2") (pin "4") (pinfunction "DIN_4") (pintype "passive"))
    )
    (net (code "16") (name "/O2") (class "Default")
      (node (ref "GRB2") (pin "2") (pinfunction "DOUT_2") (pintype "passive"))
      (node (ref "GRB3") (pin "4") (pinfunction "DIN_4") (pintype "passive"))
    )
    (net (code "17") (name "/O3") (class "Default")
      (node (ref "GRB4") (pin "2") (pinfunction "DOUT_2") (pintype "passive"))
      (node (ref "GRB5") (pin "4") (pinfunction "DIN_4") (pintype "passive"))
    )
    (net (code "18") (name "/O4") (class "Default")
      (node (ref "GRB5") (pin "2") (pinfunction "DOUT_2") (pintype "passive"))
      (node (ref "GRB6") (pin "4") (pinfunction "DIN_4") (pintype "passive"))
    )
    (net (code "19") (name "/O5") (class "Default")
      (node (ref "GRB6") (pin "2") (pinfunction "DOUT_2") (pintype "passive"))
      (node (ref "GRB7") (pin "4") (pinfunction "DIN_4") (pintype "passive"))
    )
    (net (code "20") (name "/O6") (class "Default")
      (node (ref "GRB7") (pin "2") (pinfunction "DOUT_2") (pintype "passive"))
      (node (ref "GRB8") (pin "4") (pinfunction "DIN_4") (pintype "passive"))
    )
    (net (code "21") (name "/O7") (class "Default")
      (node (ref "GRB8") (pin "2") (pinfunction "DOUT_2") (pintype "passive"))
      (node (ref "GRB9") (pin "4") (pinfunction "DIN_4") (pintype "passive"))
    )
    (net (code "22") (name "/O8") (class "Default")
      (node (ref "GRB10") (pin "4") (pinfunction "DIN_4") (pintype "passive"))
      (node (ref "GRB9") (pin "2") (pinfunction "DOUT_2") (pintype "passive"))
    )
    (net (code "23") (name "/O9") (class "Default")
      (node (ref "GRB10") (pin "2") (pinfunction "DOUT_2") (pintype "passive"))
      (node (ref "GRB11") (pin "4") (pinfunction "DIN_4") (pintype "passive"))
    )
    (net (code "24") (name "/O10") (class "Default")
      (node (ref "GRB11") (pin "2") (pinfunction "DOUT_2") (pintype "passive"))
      (node (ref "GRB12") (pin "4") (pinfunction "DIN_4") (pintype "passive"))
    )
    (net (code "25") (name "/O11") (class "Default")
      (node (ref "GRB12") (pin "2") (pinfunction "DOUT_2") (pintype "passive"))
      (node (ref "GRB13") (pin "4") (pinfunction "DIN_4") (pintype "passive"))
    )
    (net (code "26") (name "/O12") (class "Default")
      (node (ref "GRB13") (pin "2") (pinfunction "DOUT_2") (pintype "passive"))
      (node (ref "GRB14") (pin "4") (pinfunction "DIN_4") (pintype "passive"))
    )
    (net (code "27") (name "/O13") (class "Default")
      (node (ref "GRB14") (pin "2") (pinfunction "DOUT_2") (pintype "passive"))
      (node (ref "GRB15") (pin "4") (pinfunction "DIN_4") (pintype "passive"))
    )
    (net (code "28") (name "/O14") (class "Default")
      (node (ref "GRB15") (pin "2") (pinfunction "DOUT_2") (pintype "passive"))
      (node (ref "GRB16") (pin "4") (pinfunction "DIN_4") (pintype "passive"))
    )
    (net (code "29") (name "/O15") (class "Default")
      (node (ref "GRB16") (pin "2") (pinfunction "DOUT_2") (pintype "passive"))
      (node (ref "GRB17") (pin "4") (pinfunction "DIN_4") (pintype "passive"))
    )
    (net (code "30") (name "/O16") (class "Default")
      (node (ref "GRB17") (pin "2") (pinfunction "DOUT_2") (pintype "passive"))
      (node (ref "GRB18") (pin "4") (pinfunction "DIN_4") (pintype "passive"))
    )
    (net (code "31") (name "/O17") (class "Default")
      (node (ref "GRB18") (pin "2") (pinfunction "DOUT_2") (pintype "passive"))
      (node (ref "GRB19") (pin "4") (pinfunction "DIN_4") (pintype "passive"))
    )
    (net (code "32") (name "/O18") (class "Default")
      (node (ref "GRB19") (pin "2") (pinfunction "DOUT_2") (pintype "passive"))
      (node (ref "GRB20") (pin "4") (pinfunction "DIN_4") (pintype "passive"))
    )
    (net (code "33") (name "/O19") (class "Default")
      (node (ref "GRB20") (pin "2") (pinfunction "DOUT_2") (pintype "passive"))
      (node (ref "GRB21") (pin "4") (pinfunction "DIN_4") (pintype "passive"))
    )
    (net (code "34") (name "/O20") (class "Default")
      (node (ref "GRB21") (pin "2") (pinfunction "DOUT_2") (pintype "passive"))
      (node (ref "GRB22") (pin "4") (pinfunction "DIN_4") (pintype "passive"))
    )
    (net (code "35") (name "/O21") (class "Default")
      (node (ref "GRB22") (pin "2") (pinfunction "DOUT_2") (pintype "passive"))
      (node (ref "GRB23") (pin "4") (pinfunction "DIN_4") (pintype "passive"))
    )
    (net (code "36") (name "/O22") (class "Default")
      (node (ref "GRB23") (pin "2") (pinfunction "DOUT_2") (pintype "passive"))
      (node (ref "GRB24") (pin "4") (pinfunction "DIN_4") (pintype "passive"))
    )
    (net (code "37") (name "/O23") (class "Default")
      (node (ref "GRB24") (pin "2") (pinfunction "DOUT_2") (pintype "passive"))
      (node (ref "GRB25") (pin "4") (pinfunction "DIN_4") (pintype "passive"))
    )
    (net (code "38") (name "/O24") (class "Default")
      (node (ref "GRB25") (pin "2") (pinfunction "DOUT_2") (pintype "passive"))
      (node (ref "GRB26") (pin "4") (pinfunction "DIN_4") (pintype "passive"))
    )
    (net (code "39") (name "/O25") (class "Default")
      (node (ref "GRB26") (pin "2") (pinfunction "DOUT_2") (pintype "passive"))
      (node (ref "GRB27") (pin "4") (pinfunction "DIN_4") (pintype "passive"))
    )
    (net (code "40") (name "/OSC_IN") (class "Default")
      (node (ref "C14") (pin "2") (pinfunction "2_2") (pintype "passive"))
      (node (ref "U1") (pin "5") (pinfunction "PF0-OSC_IN(PF0)_5") (pintype "passive"))
      (node (ref "Y1") (pin "2") (pinfunction "2_2") (pintype "passive"))
    )
    (net (code "41") (name "/OSC_OUT") (class "Default")
      (node (ref "C18") (pin "2") (pinfunction "2_2") (pintype "passive"))
      (node (ref "U1") (pin "6") (pinfunction "PF1-OSC_OUT(PF1)_6") (pintype "passive"))
      (node (ref "Y1") (pin "1") (pinfunction "1_1") (pintype "passive"))
    )
    (net (code "42") (name "/OUT1") (class "Default")
      (node (ref "U1") (pin "33") (pinfunction "PA12_33") (pintype "passive"))
      (node (ref "U5") (pin "1") (pinfunction "OUT_1") (pintype "passive"))
    )
    (net (code "43") (name "/OUT2") (class "Default")
      (node (ref "U1") (pin "27") (pinfunction "PB14_27") (pintype "passive"))
      (node (ref "U6") (pin "1") (pinfunction "OUT_1") (pintype "passive"))
    )
    (net (code "44") (name "/OUT3") (class "Default")
      (node (ref "U1") (pin "25") (pinfunction "PB12_25") (pintype "passive"))
      (node (ref "U7") (pin "1") (pinfunction "OUT_1") (pintype "passive"))
    )
    (net (code "45") (name "/PWM") (class "Default")
      (node (ref "JP1") (pin "2") (pinfunction "2_2") (pintype "passive"))
      (node (ref "U1") (pin "45") (pinfunction "PB8_45") (pintype "passive"))
    )
    (net (code "46") (name "/RGB") (class "Default")
      (node (ref "GRB1") (pin "4") (pinfunction "DIN_4") (pintype "passive"))
      (node (ref "U1") (pin "29") (pinfunction "PA8_29") (pintype "passive"))
    )
    (net (code "47") (name "/RGB1") (class "Default")
      (node (ref "GRB4") (pin "4") (pinfunction "DIN_4") (pintype "passive"))
      (node (ref "U1") (pin "32") (pinfunction "PA11_32") (pintype "passive"))
    )
    (net (code "48") (name "/RX") (class "Default")
      (node (ref "U1") (pin "31") (pinfunction "PA10_31") (pintype "passive"))
      (node (ref "UART") (pin "3") (pinfunction "3_3") (pintype "passive"))
    )
    (net (code "49") (name "/SCL") (class "Default")
      (node (ref "C27") (pin "2") (pinfunction "2_2") (pintype "passive"))
      (node (ref "Q1") (pin "3") (pinfunction "S_3") (pintype "passive"))
      (node (ref "R7") (pin "1") (pinfunction "1_1") (pintype "passive"))
      (node (ref "U1") (pin "14") (pinfunction "PA4_14") (pintype "passive"))
    )
    (net (code "50") (name "/SDA") (class "Default")
      (node (ref "C28") (pin "2") (pinfunction "2_2") (pintype "passive"))
      (node (ref "Q2") (pin "3") (pinfunction "S_3") (pintype "passive"))
      (node (ref "R9") (pin "1") (pinfunction "1_1") (pintype "passive"))
      (node (ref "U1") (pin "15") (pinfunction "PA5_15") (pintype "passive"))
    )
    (net (code "51") (name "/SEG1") (class "Default")
      (node (ref "SMG1") (pin "11") (pinfunction "A_11") (pintype "passive"))
      (node (ref "U4") (pin "8") (pinfunction "A/KI1_8") (pintype "passive"))
    )
    (net (code "52") (name "/SEG2") (class "Default")
      (node (ref "SMG1") (pin "7") (pinfunction "B_7") (pintype "passive"))
      (node (ref "U4") (pin "16") (pinfunction "DP/KP_16") (pintype "passive"))
    )
    (net (code "53") (name "/SEG3") (class "Default")
      (node (ref "SMG1") (pin "4") (pinfunction "C_4") (pintype "passive"))
      (node (ref "U4") (pin "11") (pinfunction "C/KI3_11") (pintype "passive"))
    )
    (net (code "54") (name "/SEG4") (class "Default")
      (node (ref "SMG1") (pin "2") (pinfunction "D_2") (pintype "passive"))
      (node (ref "U4") (pin "13") (pinfunction "E/KI5_13") (pintype "passive"))
    )
    (net (code "55") (name "/SEG5") (class "Default")
      (node (ref "SMG1") (pin "1") (pinfunction "E_1") (pintype "passive"))
      (node (ref "U4") (pin "14") (pinfunction "F/KI6_14") (pintype "passive"))
    )
    (net (code "56") (name "/SEG6") (class "Default")
      (node (ref "SMG1") (pin "10") (pinfunction "F_10") (pintype "passive"))
      (node (ref "U4") (pin "15") (pinfunction "G/KI7_15") (pintype "passive"))
    )
    (net (code "57") (name "/SEG7") (class "Default")
      (node (ref "SMG1") (pin "5") (pinfunction "G_5") (pintype "passive"))
      (node (ref "U4") (pin "9") (pinfunction "B/KI2_9") (pintype "passive"))
    )
    (net (code "58") (name "/SEG8") (class "Default")
      (node (ref "SMG1") (pin "3") (pinfunction "H_3") (pintype "passive"))
      (node (ref "U4") (pin "12") (pinfunction "D/KI4_12") (pintype "passive"))
    )
    (net (code "59") (name "/SWCLK") (class "Default")
      (node (ref "SWD1") (pin "4") (pinfunction "4_4") (pintype "passive"))
      (node (ref "U1") (pin "37") (pinfunction "PA14(SWCLK)_37") (pintype "passive"))
    )
    (net (code "60") (name "/SWDIO") (class "Default")
      (node (ref "SWD1") (pin "5") (pinfunction "5_5") (pintype "passive"))
      (node (ref "U1") (pin "34") (pinfunction "PA13(SWDIO)_34") (pintype "passive"))
    )
    (net (code "61") (name "/S_SCL") (class "Default")
      (node (ref "Q1") (pin "2") (pinfunction "D_2") (pintype "passive"))
      (node (ref "R8") (pin "1") (pinfunction "1_1") (pintype "passive"))
      (node (ref "U4") (pin "2") (pinfunction "SCL_2") (pintype "passive"))
    )
    (net (code "62") (name "/S_SDA") (class "Default")
      (node (ref "Q2") (pin "2") (pinfunction "D_2") (pintype "passive"))
      (node (ref "R10") (pin "1") (pinfunction "1_1") (pintype "passive"))
      (node (ref "U4") (pin "3") (pinfunction "SDA_3") (pintype "passive"))
    )
    (net (code "63") (name "/TX") (class "Default")
      (node (ref "U1") (pin "30") (pinfunction "PA9_30") (pintype "passive"))
      (node (ref "UART") (pin "4") (pinfunction "4_4") (pintype "passive"))
    )
    (net (code "64") (name "3.3V") (class "Default")
      (node (ref "C16") (pin "2") (pinfunction "2_2") (pintype "passive"))
      (node (ref "C17") (pin "2") (pinfunction "2_2") (pintype "passive"))
      (node (ref "C35") (pin "1") (pinfunction "1_1") (pintype "passive"))
      (node (ref "C36") (pin "1") (pinfunction "1_1") (pintype "passive"))
      (node (ref "C48") (pin "2") (pinfunction "2_2") (pintype "passive"))
      (node (ref "C49") (pin "2") (pinfunction "2_2") (pintype "passive"))
      (node (ref "C5") (pin "2") (pinfunction "2_2") (pintype "passive"))
      (node (ref "C50") (pin "2") (pinfunction "2_2") (pintype "passive"))
      (node (ref "C51") (pin "2") (pinfunction "2_2") (pintype "passive"))
      (node (ref "C52") (pin "2") (pinfunction "2_2") (pintype "passive"))
      (node (ref "C53") (pin "2") (pinfunction "2_2") (pintype "passive"))
      (node (ref "C6") (pin "2") (pinfunction "2_2") (pintype "passive"))
      (node (ref "C7") (pin "2") (pinfunction "2_2") (pintype "passive"))
      (node (ref "C8") (pin "2") (pinfunction "2_2") (pintype "passive"))
      (node (ref "E2") (pin "1") (pinfunction "A_1") (pintype "passive"))
      (node (ref "E5") (pin "1") (pinfunction "A_1") (pintype "passive"))
      (node (ref "E6") (pin "1") (pinfunction "A_1") (pintype "passive"))
      (node (ref "R1") (pin "2") (pinfunction "2_2") (pintype "passive"))
      (node (ref "R11") (pin "2") (pinfunction "2_2") (pintype "passive"))
      (node (ref "R12") (pin "2") (pinfunction "2_2") (pintype "passive"))
      (node (ref "R13") (pin "1") (pinfunction "1_1") (pintype "passive"))
      (node (ref "R14") (pin "1") (pinfunction "1_1") (pintype "passive"))
      (node (ref "R17") (pin "2") (pinfunction "2_2") (pintype "passive"))
      (node (ref "R18") (pin "2") (pinfunction "2_2") (pintype "passive"))
      (node (ref "R30") (pin "2") (pinfunction "2_2") (pintype "passive"))
      (node (ref "R5") (pin "2") (pinfunction "2_2") (pintype "passive"))
      (node (ref "R6") (pin "2") (pinfunction "2_2") (pintype "passive"))
      (node (ref "R7") (pin "2") (pinfunction "2_2") (pintype "passive"))
      (node (ref "R9") (pin "2") (pinfunction "2_2") (pintype "passive"))
      (node (ref "SWD1") (pin "1") (pinfunction "1_1") (pintype "passive"))
      (node (ref "U1") (pin "1") (pinfunction "VDD_1") (pintype "passive"))
      (node (ref "U1") (pin "24") (pinfunction "VDD_24") (pintype "passive"))
      (node (ref "U1") (pin "48") (pinfunction "VDD_48") (pintype "passive"))
      (node (ref "U1") (pin "9") (pinfunction "VDDA_9") (pintype "passive"))
      (node (ref "U3") (pin "2") (pinfunction "O_2") (pintype "passive"))
      (node (ref "U5") (pin "5") (pinfunction "VCC_5") (pintype "passive"))
      (node (ref "U6") (pin "5") (pinfunction "VCC_5") (pintype "passive"))
      (node (ref "U7") (pin "5") (pinfunction "VCC_5") (pintype "passive"))
      (node (ref "UART") (pin "1") (pinfunction "1_1") (pintype "passive"))
    )
    (net (code "65") (name "5V") (class "Default")
      (node (ref "B1") (pin "1") (pinfunction "1_1") (pintype "passive"))
      (node (ref "C1") (pin "2") (pinfunction "2_2") (pintype "passive"))
      (node (ref "C10") (pin "2") (pinfunction "2_2") (pintype "passive"))
      (node (ref "C11") (pin "2") (pinfunction "2_2") (pintype "passive"))
      (node (ref "C12") (pin "2") (pinfunction "2_2") (pintype "passive"))
      (node (ref "C13") (pin "2") (pinfunction "2_2") (pintype "passive"))
      (node (ref "C15") (pin "2") (pinfunction "2_2") (pintype "passive"))
      (node (ref "C19") (pin "2") (pinfunction "2_2") (pintype "passive"))
      (node (ref "C2") (pin "2") (pinfunction "2_2") (pintype "passive"))
      (node (ref "C20") (pin "2") (pinfunction "2_2") (pintype "passive"))
      (node (ref "C21") (pin "2") (pinfunction "2_2") (pintype "passive"))
      (node (ref "C22") (pin "2") (pinfunction "2_2") (pintype "passive"))
      (node (ref "C23") (pin "2") (pinfunction "2_2") (pintype "passive"))
      (node (ref "C24") (pin "2") (pinfunction "2_2") (pintype "passive"))
      (node (ref "C25") (pin "2") (pinfunction "2_2") (pintype "passive"))
      (node (ref "C26") (pin "2") (pinfunction "2_2") (pintype "passive"))
      (node (ref "C29") (pin "2") (pinfunction "2_2") (pintype "passive"))
      (node (ref "C3") (pin "2") (pinfunction "2_2") (pintype "passive"))
      (node (ref "C30") (pin "2") (pinfunction "2_2") (pintype "passive"))
      (node (ref "C31") (pin "2") (pinfunction "2_2") (pintype "passive"))
      (node (ref "C32") (pin "2") (pinfunction "2_2") (pintype "passive"))
      (node (ref "C33") (pin "2") (pinfunction "2_2") (pintype "passive"))
      (node (ref "C34") (pin "2") (pinfunction "2_2") (pintype "passive"))
      (node (ref "C37") (pin "2") (pinfunction "2_2") (pintype "passive"))
      (node (ref "C38") (pin "2") (pinfunction "2_2") (pintype "passive"))
      (node (ref "C39") (pin "2") (pinfunction "2_2") (pintype "passive"))
      (node (ref "C40") (pin "2") (pinfunction "2_2") (pintype "passive"))
      (node (ref "C41") (pin "2") (pinfunction "2_2") (pintype "passive"))
      (node (ref "C42") (pin "2") (pinfunction "2_2") (pintype "passive"))
      (node (ref "C43") (pin "2") (pinfunction "2_2") (pintype "passive"))
      (node (ref "C44") (pin "2") (pinfunction "2_2") (pintype "passive"))
      (node (ref "E3") (pin "1") (pinfunction "A_1") (pintype "passive"))
      (node (ref "E4") (pin "1") (pinfunction "A_1") (pintype "passive"))
      (node (ref "GRB1") (pin "1") (pinfunction "VDD_1") (pintype "passive"))
      (node (ref "GRB10") (pin "1") (pinfunction "VDD_1") (pintype "passive"))
      (node (ref "GRB11") (pin "1") (pinfunction "VDD_1") (pintype "passive"))
      (node (ref "GRB12") (pin "1") (pinfunction "VDD_1") (pintype "passive"))
      (node (ref "GRB13") (pin "1") (pinfunction "VDD_1") (pintype "passive"))
      (node (ref "GRB14") (pin "1") (pinfunction "VDD_1") (pintype "passive"))
      (node (ref "GRB15") (pin "1") (pinfunction "VDD_1") (pintype "passive"))
      (node (ref "GRB16") (pin "1") (pinfunction "VDD_1") (pintype "passive"))
      (node (ref "GRB17") (pin "1") (pinfunction "VDD_1") (pintype "passive"))
      (node (ref "GRB18") (pin "1") (pinfunction "VDD_1") (pintype "passive"))
      (node (ref "GRB19") (pin "1") (pinfunction "VDD_1") (pintype "passive"))
      (node (ref "GRB2") (pin "1") (pinfunction "VDD_1") (pintype "passive"))
      (node (ref "GRB20") (pin "1") (pinfunction "VDD_1") (pintype "passive"))
      (node (ref "GRB21") (pin "1") (pinfunction "VDD_1") (pintype "passive"))
      (node (ref "GRB22") (pin "1") (pinfunction "VDD_1") (pintype "passive"))
      (node (ref "GRB23") (pin "1") (pinfunction "VDD_1") (pintype "passive"))
      (node (ref "GRB24") (pin "1") (pinfunction "VDD_1") (pintype "passive"))
      (node (ref "GRB25") (pin "1") (pinfunction "VDD_1") (pintype "passive"))
      (node (ref "GRB26") (pin "1") (pinfunction "VDD_1") (pintype "passive"))
      (node (ref "GRB27") (pin "1") (pinfunction "VDD_1") (pintype "passive"))
      (node (ref "GRB3") (pin "1") (pinfunction "VDD_1") (pintype "passive"))
      (node (ref "GRB4") (pin "1") (pinfunction "VDD_1") (pintype "passive"))
      (node (ref "GRB5") (pin "1") (pinfunction "VDD_1") (pintype "passive"))
      (node (ref "GRB6") (pin "1") (pinfunction "VDD_1") (pintype "passive"))
      (node (ref "GRB7") (pin "1") (pinfunction "VDD_1") (pintype "passive"))
      (node (ref "GRB8") (pin "1") (pinfunction "VDD_1") (pintype "passive"))
      (node (ref "GRB9") (pin "1") (pinfunction "VDD_1") (pintype "passive"))
      (node (ref "L1") (pin "2") (pinfunction "2_2") (pintype "passive"))
      (node (ref "R10") (pin "2") (pinfunction "2_2") (pintype "passive"))
      (node (ref "R2") (pin "2") (pinfunction "2_2") (pintype "passive"))
      (node (ref "R8") (pin "2") (pinfunction "2_2") (pintype "passive"))
      (node (ref "U3") (pin "3") (pinfunction "I_3") (pintype "passive"))
      (node (ref "U4") (pin "10") (pinfunction "VDD_10") (pintype "passive"))
    )
    (net (code "66") (name "12V") (class "Default")
      (node (ref "E1") (pin "1") (pinfunction "A_1") (pintype "passive"))
      (node (ref "E7") (pin "1") (pinfunction "A_1") (pintype "passive"))
      (node (ref "Q6") (pin "3") (pinfunction "S_3") (pintype "passive"))
      (node (ref "R28") (pin "2") (pinfunction "2_2") (pintype "passive"))
      (node (ref "R3") (pin "1") (pinfunction "1_1") (pintype "passive"))
      (node (ref "U2") (pin "5") (pinfunction "IN_5") (pintype "passive"))
      (node (ref "VD1") (pin "2") (pinfunction "K_2") (pintype "passive"))
    )
    (net (code "67") (name "ETX_12V") (class "Default")
      (node (ref "CON1") (pin "1") (pintype "power_in"))
      (node (ref "VD1") (pin "1") (pinfunction "A_1") (pintype "passive"))
    )
    (net (code "68") (name "GND") (class "Default")
      (node (ref "C1") (pin "1") (pinfunction "1_1") (pintype "passive"))
      (node (ref "C10") (pin "1") (pinfunction "1_1") (pintype "passive"))
      (node (ref "C11") (pin "1") (pinfunction "1_1") (pintype "passive"))
      (node (ref "C12") (pin "1") (pinfunction "1_1") (pintype "passive"))
      (node (ref "C13") (pin "1") (pinfunction "1_1") (pintype "passive"))
      (node (ref "C14") (pin "1") (pinfunction "1_1") (pintype "passive"))
      (node (ref "C15") (pin "1") (pinfunction "1_1") (pintype "passive"))
      (node (ref "C16") (pin "1") (pinfunction "1_1") (pintype "passive"))
      (node (ref "C17") (pin "1") (pinfunction "1_1") (pintype "passive"))
      (node (ref "C18") (pin "1") (pinfunction "1_1") (pintype "passive"))
      (node (ref "C19") (pin "1") (pinfunction "1_1") (pintype "passive"))
      (node (ref "C2") (pin "1") (pinfunction "1_1") (pintype "passive"))
      (node (ref "C20") (pin "1") (pinfunction "1_1") (pintype "passive"))
      (node (ref "C21") (pin "1") (pinfunction "1_1") (pintype "passive"))
      (node (ref "C22") (pin "1") (pinfunction "1_1") (pintype "passive"))
      (node (ref "C23") (pin "1") (pinfunction "1_1") (pintype "passive"))
      (node (ref "C24") (pin "1") (pinfunction "1_1") (pintype "passive"))
      (node (ref "C25") (pin "1") (pinfunction "1_1") (pintype "passive"))
      (node (ref "C26") (pin "1") (pinfunction "1_1") (pintype "passive"))
      (node (ref "C27") (pin "1") (pinfunction "1_1") (pintype "passive"))
      (node (ref "C28") (pin "1") (pinfunction "1_1") (pintype "passive"))
      (node (ref "C29") (pin "1") (pinfunction "1_1") (pintype "passive"))
      (node (ref "C3") (pin "1") (pinfunction "1_1") (pintype "passive"))
      (node (ref "C30") (pin "1") (pinfunction "1_1") (pintype "passive"))
      (node (ref "C31") (pin "1") (pinfunction "1_1") (pintype "passive"))
      (node (ref "C32") (pin "1") (pinfunction "1_1") (pintype "passive"))
      (node (ref "C33") (pin "1") (pinfunction "1_1") (pintype "passive"))
      (node (ref "C34") (pin "1") (pinfunction "1_1") (pintype "passive"))
      (node (ref "C35") (pin "2") (pinfunction "2_2") (pintype "passive"))
      (node (ref "C36") (pin "2") (pinfunction "2_2") (pintype "passive"))
      (node (ref "C37") (pin "1") (pinfunction "1_1") (pintype "passive"))
      (node (ref "C38") (pin "1") (pinfunction "1_1") (pintype "passive"))
      (node (ref "C39") (pin "1") (pinfunction "1_1") (pintype "passive"))
      (node (ref "C40") (pin "1") (pinfunction "1_1") (pintype "passive"))
      (node (ref "C41") (pin "1") (pinfunction "1_1") (pintype "passive"))
      (node (ref "C42") (pin "1") (pinfunction "1_1") (pintype "passive"))
      (node (ref "C43") (pin "1") (pinfunction "1_1") (pintype "passive"))
      (node (ref "C44") (pin "1") (pinfunction "1_1") (pintype "passive"))
      (node (ref "C45") (pin "2") (pinfunction "2_2") (pintype "passive"))
      (node (ref "C46") (pin "2") (pinfunction "2_2") (pintype "passive"))
      (node (ref "C47") (pin "2") (pinfunction "2_2") (pintype "passive"))
      (node (ref "C48") (pin "1") (pinfunction "1_1") (pintype "passive"))
      (node (ref "C49") (pin "1") (pinfunction "1_1") (pintype "passive"))
      (node (ref "C5") (pin "1") (pinfunction "1_1") (pintype "passive"))
      (node (ref "C50") (pin "1") (pinfunction "1_1") (pintype "passive"))
      (node (ref "C51") (pin "1") (pinfunction "1_1") (pintype "passive"))
      (node (ref "C52") (pin "1") (pinfunction "1_1") (pintype "passive"))
      (node (ref "C53") (pin "1") (pinfunction "1_1") (pintype "passive"))
      (node (ref "C6") (pin "1") (pinfunction "1_1") (pintype "passive"))
      (node (ref "C7") (pin "1") (pinfunction "1_1") (pintype "passive"))
      (node (ref "C8") (pin "1") (pinfunction "1_1") (pintype "passive"))
      (node (ref "C9") (pin "1") (pinfunction "1_1") (pintype "passive"))
      (node (ref "CON1") (pin "2") (pintype "power_in"))
      (node (ref "E1") (pin "2") (pinfunction "K_2") (pintype "passive"))
      (node (ref "E2") (pin "2") (pinfunction "K_2") (pintype "passive"))
      (node (ref "E3") (pin "2") (pinfunction "K_2") (pintype "passive"))
      (node (ref "E4") (pin "2") (pinfunction "K_2") (pintype "passive"))
      (node (ref "E5") (pin "2") (pinfunction "K_2") (pintype "passive"))
      (node (ref "E6") (pin "2") (pinfunction "K_2") (pintype "passive"))
      (node (ref "E7") (pin "2") (pinfunction "K_2") (pintype "passive"))
      (node (ref "GRB1") (pin "3") (pinfunction "GND_3") (pintype "passive"))
      (node (ref "GRB10") (pin "3") (pinfunction "GND_3") (pintype "passive"))
      (node (ref "GRB11") (pin "3") (pinfunction "GND_3") (pintype "passive"))
      (node (ref "GRB12") (pin "3") (pinfunction "GND_3") (pintype "passive"))
      (node (ref "GRB13") (pin "3") (pinfunction "GND_3") (pintype "passive"))
      (node (ref "GRB14") (pin "3") (pinfunction "GND_3") (pintype "passive"))
      (node (ref "GRB15") (pin "3") (pinfunction "GND_3") (pintype "passive"))
      (node (ref "GRB16") (pin "3") (pinfunction "GND_3") (pintype "passive"))
      (node (ref "GRB17") (pin "3") (pinfunction "GND_3") (pintype "passive"))
      (node (ref "GRB18") (pin "3") (pinfunction "GND_3") (pintype "passive"))
      (node (ref "GRB19") (pin "3") (pinfunction "GND_3") (pintype "passive"))
      (node (ref "GRB2") (pin "3") (pinfunction "GND_3") (pintype "passive"))
      (node (ref "GRB20") (pin "3") (pinfunction "GND_3") (pintype "passive"))
      (node (ref "GRB21") (pin "3") (pinfunction "GND_3") (pintype "passive"))
      (node (ref "GRB22") (pin "3") (pinfunction "GND_3") (pintype "passive"))
      (node (ref "GRB23") (pin "3") (pinfunction "GND_3") (pintype "passive"))
      (node (ref "GRB24") (pin "3") (pinfunction "GND_3") (pintype "passive"))
      (node (ref "GRB25") (pin "3") (pinfunction "GND_3") (pintype "passive"))
      (node (ref "GRB26") (pin "3") (pinfunction "GND_3") (pintype "passive"))
      (node (ref "GRB27") (pin "3") (pinfunction "GND_3") (pintype "passive"))
      (node (ref "GRB3") (pin "3") (pinfunction "GND_3") (pintype "passive"))
      (node (ref "GRB4") (pin "3") (pinfunction "GND_3") (pintype "passive"))
      (node (ref "GRB5") (pin "3") (pinfunction "GND_3") (pintype "passive"))
      (node (ref "GRB6") (pin "3") (pinfunction "GND_3") (pintype "passive"))
      (node (ref "GRB7") (pin "3") (pinfunction "GND_3") (pintype "passive"))
      (node (ref "GRB8") (pin "3") (pinfunction "GND_3") (pintype "passive"))
      (node (ref "GRB9") (pin "3") (pinfunction "GND_3") (pintype "passive"))
      (node (ref "JP1") (pin "4") (pinfunction "4_4") (pintype "passive"))
      (node (ref "Q3") (pin "2") (pinfunction "e_2") (pintype "passive"))
      (node (ref "Q4") (pin "2") (pinfunction "e_2") (pintype "passive"))
      (node (ref "Q5") (pin "2") (pinfunction "e_2") (pintype "passive"))
      (node (ref "Q7") (pin "2") (pinfunction "e_2") (pintype "passive"))
      (node (ref "R22") (pin "1") (pinfunction "1_1") (pintype "passive"))
      (node (ref "R23") (pin "1") (pinfunction "1_1") (pintype "passive"))
      (node (ref "R24") (pin "1") (pinfunction "1_1") (pintype "passive"))
      (node (ref "R4") (pin "1") (pinfunction "1_1") (pintype "passive"))
      (node (ref "REC1") (pin "2") (pinfunction "GND_2") (pintype "passive"))
      (node (ref "REC2") (pin "2") (pinfunction "GND_2") (pintype "passive"))
      (node (ref "SWD1") (pin "2") (pinfunction "2_2") (pintype "passive"))
      (node (ref "U1") (pin "23") (pinfunction "VSS_23") (pintype "passive"))
      (node (ref "U1") (pin "44") (pinfunction "BOOT0_44") (pintype "passive"))
      (node (ref "U1") (pin "47") (pinfunction "VSS_47") (pintype "passive"))
      (node (ref "U1") (pin "8") (pinfunction "VSSA_8") (pintype "passive"))
      (node (ref "U2") (pin "2") (pinfunction "GND_2") (pintype "passive"))
      (node (ref "U3") (pin "1") (pinfunction "G_1") (pintype "passive"))
      (node (ref "U4") (pin "4") (pinfunction "GND_4") (pintype "passive"))
      (node (ref "U5") (pin "2") (pinfunction "GND_2") (pintype "passive"))
      (node (ref "U6") (pin "2") (pinfunction "GND_2") (pintype "passive"))
      (node (ref "U7") (pin "2") (pinfunction "GND_2") (pintype "passive"))
      (node (ref "UART") (pin "2") (pinfunction "2_2") (pintype "passive"))
      (node (ref "VD2") (pin "1") (pinfunction "A_1") (pintype "passive"))
    )
    (net (code "69") (name "Net-(D1-A)") (class "Default")
      (node (ref "D1") (pin "1") (pinfunction "A_1") (pintype "passive"))
      (node (ref "R13") (pin "2") (pinfunction "2_2") (pintype "passive"))
    )
    (net (code "70") (name "Net-(D1-K)") (class "Default")
      (node (ref "D1") (pin "2") (pinfunction "K_2") (pintype "passive"))
      (node (ref "Q4") (pin "3") (pinfunction "c_3") (pintype "passive"))
    )
    (net (code "71") (name "Net-(D2-A)") (class "Default")
      (node (ref "D2") (pin "1") (pinfunction "A_1") (pintype "passive"))
      (node (ref "R14") (pin "2") (pinfunction "2_2") (pintype "passive"))
    )
    (net (code "72") (name "Net-(D2-K)") (class "Default")
      (node (ref "D2") (pin "2") (pinfunction "K_2") (pintype "passive"))
      (node (ref "Q5") (pin "3") (pinfunction "c_3") (pintype "passive"))
    )
    (net (code "73") (name "Net-(Q1-G)") (class "Default")
      (node (ref "Q1") (pin "1") (pinfunction "G_1") (pintype "passive"))
      (node (ref "R5") (pin "1") (pinfunction "1_1") (pintype "passive"))
    )
    (net (code "74") (name "Net-(Q2-G)") (class "Default")
      (node (ref "Q2") (pin "1") (pinfunction "G_1") (pintype "passive"))
      (node (ref "R6") (pin "1") (pinfunction "1_1") (pintype "passive"))
    )
    (net (code "75") (name "Net-(Q3-b)") (class "Default")
      (node (ref "Q3") (pin "1") (pinfunction "b_1") (pintype "passive"))
      (node (ref "R19") (pin "2") (pinfunction "2_2") (pintype "passive"))
      (node (ref "R22") (pin "2") (pinfunction "2_2") (pintype "passive"))
    )
    (net (code "76") (name "Net-(Q3-c)") (class "Default")
      (node (ref "B1") (pin "2") (pinfunction "2_2") (pintype "passive"))
      (node (ref "Q3") (pin "3") (pinfunction "c_3") (pintype "passive"))
    )
    (net (code "77") (name "Net-(Q4-b)") (class "Default")
      (node (ref "Q4") (pin "1") (pinfunction "b_1") (pintype "passive"))
      (node (ref "R20") (pin "2") (pinfunction "2_2") (pintype "passive"))
      (node (ref "R23") (pin "2") (pinfunction "2_2") (pintype "passive"))
    )
    (net (code "78") (name "Net-(Q5-b)") (class "Default")
      (node (ref "Q5") (pin "1") (pinfunction "b_1") (pintype "passive"))
      (node (ref "R21") (pin "2") (pinfunction "2_2") (pintype "passive"))
      (node (ref "R24") (pin "2") (pinfunction "2_2") (pintype "passive"))
    )
    (net (code "79") (name "Net-(Q6-G)") (class "Default")
      (node (ref "Q6") (pin "1") (pinfunction "G_1") (pintype "passive"))
      (node (ref "R28") (pin "1") (pinfunction "1_1") (pintype "passive"))
      (node (ref "R29") (pin "2") (pinfunction "2_2") (pintype "passive"))
    )
    (net (code "80") (name "Net-(Q7-b)") (class "Default")
      (node (ref "Q7") (pin "1") (pinfunction "b_1") (pintype "passive"))
      (node (ref "R31") (pin "2") (pinfunction "2_2") (pintype "passive"))
    )
    (net (code "81") (name "Net-(Q7-c)") (class "Default")
      (node (ref "Q7") (pin "3") (pinfunction "c_3") (pintype "passive"))
      (node (ref "R29") (pin "1") (pinfunction "1_1") (pintype "passive"))
    )
    (net (code "82") (name "Net-(R25-Pad1)") (class "Default")
      (node (ref "R25") (pin "1") (pinfunction "1_1") (pintype "passive"))
      (node (ref "T1") (pin "1") (pintype "passive"))
    )
    (net (code "83") (name "Net-(R26-Pad1)") (class "Default")
      (node (ref "R26") (pin "1") (pinfunction "1_1") (pintype "passive"))
      (node (ref "T2") (pin "1") (pintype "passive"))
    )
    (net (code "84") (name "Net-(R27-Pad1)") (class "Default")
      (node (ref "R27") (pin "1") (pinfunction "1_1") (pintype "passive"))
      (node (ref "T3") (pin "1") (pintype "passive"))
    )
    (net (code "85") (name "Net-(REC1-OUT)") (class "Default")
      (node (ref "R11") (pin "1") (pinfunction "1_1") (pintype "passive"))
      (node (ref "R15") (pin "1") (pinfunction "1_1") (pintype "passive"))
      (node (ref "REC1") (pin "1") (pinfunction "OUT_1") (pintype "passive"))
    )
    (net (code "86") (name "Net-(REC1-VCC)") (class "Default")
      (node (ref "R17") (pin "1") (pinfunction "1_1") (pintype "passive"))
      (node (ref "REC1") (pin "3") (pinfunction "VCC_3") (pintype "passive"))
    )
    (net (code "87") (name "Net-(REC2-OUT)") (class "Default")
      (node (ref "R12") (pin "1") (pinfunction "1_1") (pintype "passive"))
      (node (ref "R16") (pin "1") (pinfunction "1_1") (pintype "passive"))
      (node (ref "REC2") (pin "1") (pinfunction "OUT_1") (pintype "passive"))
    )
    (net (code "88") (name "Net-(REC2-VCC)") (class "Default")
      (node (ref "R18") (pin "1") (pinfunction "1_1") (pintype "passive"))
      (node (ref "REC2") (pin "3") (pinfunction "VCC_3") (pintype "passive"))
    )
    (net (code "89") (name "Net-(U2-BS)") (class "Default")
      (node (ref "C4") (pin "1") (pinfunction "1_1") (pintype "passive"))
      (node (ref "U2") (pin "1") (pinfunction "BS_1") (pintype "passive"))
    )
    (net (code "90") (name "Net-(U2-EN)") (class "Default")
      (node (ref "R3") (pin "2") (pinfunction "2_2") (pintype "passive"))
      (node (ref "U2") (pin "4") (pinfunction "EN_4") (pintype "passive"))
    )
    (net (code "91") (name "Net-(U2-FB)") (class "Default")
      (node (ref "R2") (pin "1") (pinfunction "1_1") (pintype "passive"))
      (node (ref "R4") (pin "2") (pinfunction "2_2") (pintype "passive"))
      (node (ref "U2") (pin "3") (pinfunction "FB_3") (pintype "passive"))
    )
    (net (code "92") (name "Net-(U2-SW)") (class "Default")
      (node (ref "C4") (pin "2") (pinfunction "2_2") (pintype "passive"))
      (node (ref "L1") (pin "1") (pinfunction "1_1") (pintype "passive"))
      (node (ref "U2") (pin "6") (pinfunction "SW_6") (pintype "passive"))
    )
    (net (code "93") (name "Net-(U5-KEY)") (class "Default")
      (node (ref "R25") (pin "2") (pinfunction "2_2") (pintype "passive"))
      (node (ref "U5") (pin "3") (pinfunction "KEY_3") (pintype "passive"))
    )
    (net (code "94") (name "Net-(U5-TOG)") (class "Default")
      (node (ref "C45") (pin "1") (pinfunction "1_1") (pintype "passive"))
      (node (ref "U5") (pin "6") (pinfunction "TOG_6") (pintype "passive"))
    )
    (net (code "95") (name "Net-(U6-KEY)") (class "Default")
      (node (ref "R26") (pin "2") (pinfunction "2_2") (pintype "passive"))
      (node (ref "U6") (pin "3") (pinfunction "KEY_3") (pintype "passive"))
    )
    (net (code "96") (name "Net-(U6-TOG)") (class "Default")
      (node (ref "C46") (pin "1") (pinfunction "1_1") (pintype "passive"))
      (node (ref "U6") (pin "6") (pinfunction "TOG_6") (pintype "passive"))
    )
    (net (code "97") (name "Net-(U7-KEY)") (class "Default")
      (node (ref "R27") (pin "2") (pinfunction "2_2") (pintype "passive"))
      (node (ref "U7") (pin "3") (pinfunction "KEY_3") (pintype "passive"))
    )
    (net (code "98") (name "Net-(U7-TOG)") (class "Default")
      (node (ref "C47") (pin "1") (pinfunction "1_1") (pintype "passive"))
      (node (ref "U7") (pin "6") (pinfunction "TOG_6") (pintype "passive"))
    )
    (net (code "99") (name "unconnected-(CON1-Pad3)") (class "Default")
      (node (ref "CON1") (pin "3") (pintype "power_in+no_connect"))
    )
    (net (code "100") (name "unconnected-(GRB3-DOUT-Pad2)") (class "Default")
      (node (ref "GRB3") (pin "2") (pinfunction "DOUT_2") (pintype "passive"))
    )
    (net (code "101") (name "unconnected-(GRB27-DOUT-Pad2)") (class "Default")
      (node (ref "GRB27") (pin "2") (pinfunction "DOUT_2") (pintype "passive"))
    )
    (net (code "102") (name "unconnected-(U1A-PA0-Pad10)") (class "Default")
      (node (ref "U1") (pin "10") (pinfunction "PA0_10") (pintype "passive"))
    )
    (net (code "103") (name "unconnected-(U1A-PA1-Pad11)") (class "Default")
      (node (ref "U1") (pin "11") (pinfunction "PA1_11") (pintype "passive"))
    )
    (net (code "104") (name "unconnected-(U1A-PB0-Pad18)") (class "Default")
      (node (ref "U1") (pin "18") (pinfunction "PB0_18") (pintype "passive"))
    )
    (net (code "105") (name "unconnected-(U1A-PB1-Pad19)") (class "Default")
      (node (ref "U1") (pin "19") (pinfunction "PB1_19") (pintype "passive"))
    )
    (net (code "106") (name "unconnected-(U1A-PB2-Pad20)") (class "Default")
      (node (ref "U1") (pin "20") (pinfunction "PB2_20") (pintype "passive"))
    )
    (net (code "107") (name "unconnected-(U1A-PB5-Pad41)") (class "Default")
      (node (ref "U1") (pin "41") (pinfunction "PB5_41") (pintype "passive"))
    )
    (net (code "108") (name "unconnected-(U1A-PB6-Pad42)") (class "Default")
      (node (ref "U1") (pin "42") (pinfunction "PB6_42") (pintype "passive"))
    )
    (net (code "109") (name "unconnected-(U1A-PB7-Pad43)") (class "Default")
      (node (ref "U1") (pin "43") (pinfunction "PB7_43") (pintype "passive"))
    )
    (net (code "110") (name "unconnected-(U1A-PB10-Pad21)") (class "Default")
      (node (ref "U1") (pin "21") (pinfunction "PB10_21") (pintype "passive"))
    )
    (net (code "111") (name "unconnected-(U1A-PB11-Pad22)") (class "Default")
      (node (ref "U1") (pin "22") (pinfunction "PB11_22") (pintype "passive"))
    )
    (net (code "112") (name "unconnected-(U1A-PB13-Pad26)") (class "Default")
      (node (ref "U1") (pin "26") (pinfunction "PB13_26") (pintype "passive"))
    )
    (net (code "113") (name "unconnected-(U1A-PB15-Pad28)") (class "Default")
      (node (ref "U1") (pin "28") (pinfunction "PB15_28") (pintype "passive"))
    )
    (net (code "114") (name "unconnected-(U1A-PC13-Pad2)") (class "Default")
      (node (ref "U1") (pin "2") (pinfunction "PC13_2") (pintype "passive"))
    )
    (net (code "115") (name "unconnected-(U1A-PC14-OSC32_IN(PC14)-Pad3)") (class "Default")
      (node (ref "U1") (pin "3") (pinfunction "PC14-OSC32_IN(PC14)_3") (pintype "passive"))
    )
    (net (code "116") (name "unconnected-(U1A-PC15-OSC32_OUT(PC15)-Pad4)") (class "Default")
      (node (ref "U1") (pin "4") (pinfunction "PC15-OSC32_OUT(PC15)_4") (pintype "passive"))
    )
    (net (code "117") (name "unconnected-(U1A-PF6-Pad35)") (class "Default")
      (node (ref "U1") (pin "35") (pinfunction "PF6_35") (pintype "passive"))
    )
    (net (code "118") (name "unconnected-(U1A-PF7-Pad36)") (class "Default")
      (node (ref "U1") (pin "36") (pinfunction "PF7_36") (pintype "passive"))
    )
    (net (code "119") (name "unconnected-(U5-AHLB-Pad4)") (class "Default")
      (node (ref "U5") (pin "4") (pinfunction "AHLB_4") (pintype "passive"))
    )
    (net (code "120") (name "unconnected-(U6-AHLB-Pad4)") (class "Default")
      (node (ref "U6") (pin "4") (pinfunction "AHLB_4") (pintype "passive"))
    )
    (net (code "121") (name "unconnected-(U7-AHLB-Pad4)") (class "Default")
      (node (ref "U7") (pin "4") (pinfunction "AHLB_4") (pintype "passive"))
    )
  )
)
